# MAIN.net
KiCad netlist of a schematic drawn in Altium Designer
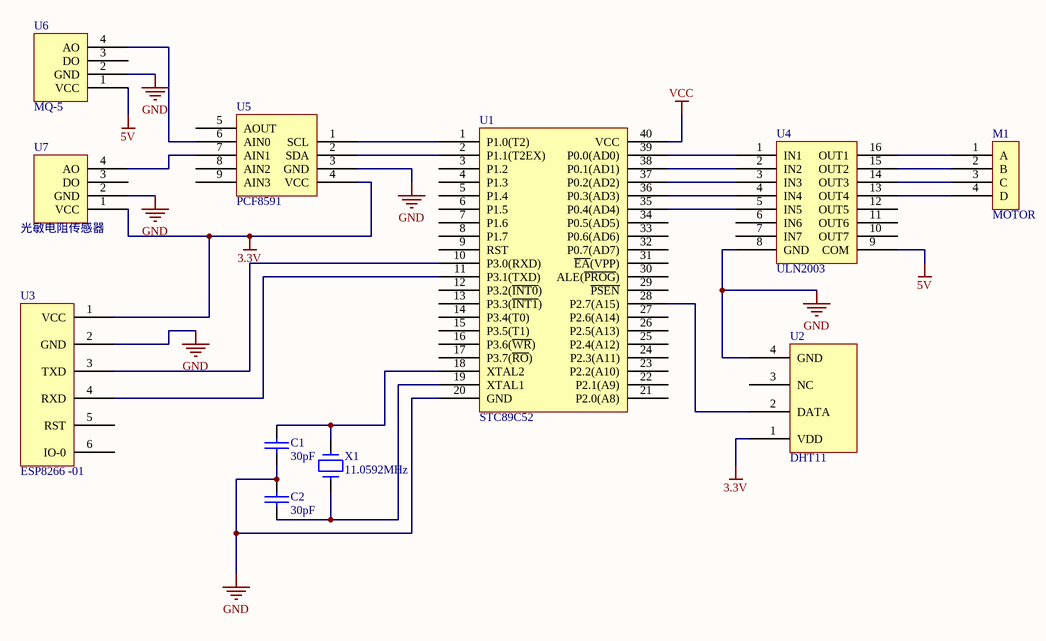
[diagram p0: MAIN.SchDoc]

(export (version "E")
  (design (tool "Eeschema 10.0.6"))
  (components
    (comp (ref "C1") (value "30pF") (footprint "RAD-0.1") (libsource (lib "温度") (part "CAP")))
    (comp (ref "C2") (value "30pF") (footprint "RAD-0.1") (libsource (lib "温度") (part "CAP")))
    (comp (ref "M1") (value "MOTOR") (libsource (lib "main") (part "MOTOR")))
    (comp (ref "U1") (value "STC89C52") (footprint "DIP40") (libsource (lib "温度") (part "89C52")))
    (comp (ref "U2") (value "DHT11") (footprint "P04A") (libsource (lib "main") (part "DHT11")))
    (comp (ref "U3") (value "ESP8266 -01") (footprint "P04A") (libsource (lib "main") (part "ESP8266 -01")))
    (comp (ref "U4") (value "ULN2003") (libsource (lib "main") (part "ULN2003")))
    (comp (ref "U5") (value "PCF8591") (libsource (lib "main") (part "PCF8591")))
    (comp (ref "U6") (value "MQ-5") (libsource (lib "main") (part "MQ-5")))
    (comp (ref "U7") (value "光敏电阻传感器") (libsource (lib "main") (part "光敏电阻传感器")))
    (comp (ref "X1") (value "11.0592MHz") (footprint "XTAL") (libsource (lib "温度") (part "CRYSTAL")))
  )
  (nets
    (net (code "1") (name "3.3V") (class "Default")
      (node (ref "U2") (pin "1") (pinfunction "VDD_1") (pintype "passive"))
      (node (ref "U3") (pin "1") (pinfunction "VCC_1") (pintype "passive"))
      (node (ref "U5") (pin "4") (pinfunction "VCC_4") (pintype "passive"))
      (node (ref "U7") (pin "1") (pinfunction "VCC_1") (pintype "passive"))
    )
    (net (code "2") (name "5V") (class "Default")
      (node (ref "U4") (pin "9") (pinfunction "COM_9") (pintype "passive"))
      (node (ref "U6") (pin "1") (pinfunction "VCC_1") (pintype "passive"))
    )
    (net (code "3") (name "GND") (class "Default")
      (node (ref "C1") (pin "2") (pinfunction "2_2") (pintype "passive"))
      (node (ref "C2") (pin "1") (pinfunction "1_1") (pintype "passive"))
      (node (ref "U1") (pin "20") (pinfunction "GND_20") (pintype "passive"))
      (node (ref "U2") (pin "4") (pinfunction "GND_4") (pintype "passive"))
      (node (ref "U3") (pin "2") (pinfunction "GND_2") (pintype "passive"))
      (node (ref "U4") (pin "8") (pinfunction "GND_8") (pintype "passive"))
      (node (ref "U5") (pin "3") (pinfunction "GND_3") (pintype "passive"))
      (node (ref "U6") (pin "2") (pinfunction "GND_2") (pintype "passive"))
      (node (ref "U7") (pin "2") (pinfunction "GND_2") (pintype "passive"))
    )
    (net (code "4") (name "Net-(M1-A)") (class "Default")
      (node (ref "M1") (pin "1") (pinfunction "A_1") (pintype "passive"))
      (node (ref "U4") (pin "16") (pinfunction "OUT1_16") (pintype "passive"))
    )
    (net (code "5") (name "Net-(M1-B)") (class "Default")
      (node (ref "M1") (pin "2") (pinfunction "B_2") (pintype "passive"))
      (node (ref "U4") (pin "15") (pinfunction "OUT2_15") (pintype "passive"))
    )
    (net (code "6") (name "Net-(M1-C)") (class "Default")
      (node (ref "M1") (pin "3") (pinfunction "C_3") (pintype "passive"))
      (node (ref "U4") (pin "14") (pinfunction "OUT3_14") (pintype "passive"))
    )
    (net (code "7") (name "Net-(M1-D)") (class "Default")
      (node (ref "M1") (pin "4") (pinfunction "D_4") (pintype "passive"))
      (node (ref "U4") (pin "13") (pinfunction "OUT4_13") (pintype "passive"))
    )
    (net (code "8") (name "Net-(U1-P0.0(AD0))") (class "Default")
      (node (ref "U1") (pin "39") (pinfunction "P0.0(AD0)_39") (pintype "passive"))
      (node (ref "U4") (pin "1") (pinfunction "IN1_1") (pintype "passive"))
    )
    (net (code "9") (name "Net-(U1-P0.1(AD1))") (class "Default")
      (node (ref "U1") (pin "38") (pinfunction "P0.1(AD1)_38") (pintype "passive"))
      (node (ref "U4") (pin "2") (pinfunction "IN2_2") (pintype "passive"))
    )
    (net (code "10") (name "Net-(U1-P0.2(AD2))") (class "Default")
      (node (ref "U1") (pin "37") (pinfunction "P0.2(AD2)_37") (pintype "passive"))
      (node (ref "U4") (pin "3") (pinfunction "IN3_3") (pintype "passive"))
    )
    (net (code "11") (name "Net-(U1-P0.3(AD3))") (class "Default")
      (node (ref "U1") (pin "36") (pinfunction "P0.3(AD3)_36") (pintype "passive"))
      (node (ref "U4") (pin "4") (pinfunction "IN4_4") (pintype "passive"))
    )
    (net (code "12") (name "Net-(U1-P0.4(AD4))") (class "Default")
      (node (ref "U1") (pin "35") (pinfunction "P0.4(AD4)_35") (pintype "passive"))
      (node (ref "U4") (pin "5") (pinfunction "IN5_5") (pintype "passive"))
    )
    (net (code "13") (name "Net-(U1-P1.0(T2))") (class "Default")
      (node (ref "U1") (pin "1") (pinfunction "P1.0(T2)_1") (pintype "passive"))
      (node (ref "U5") (pin "1") (pinfunction "SCL_1") (pintype "passive"))
    )
    (net (code "14") (name "Net-(U1-P1.1(T2EX))") (class "Default")
      (node (ref "U1") (pin "2") (pinfunction "P1.1(T2EX)_2") (pintype "passive"))
      (node (ref "U5") (pin "2") (pinfunction "SDA_2") (pintype "passive"))
    )
    (net (code "15") (name "Net-(U1-P2.7(A15))") (class "Default")
      (node (ref "U1") (pin "28") (pinfunction "P2.7(A15)_28") (pintype "passive"))
      (node (ref "U2") (pin "2") (pinfunction "DATA_2") (pintype "passive"))
    )
    (net (code "16") (name "Net-(U1-P3.0(RXD))") (class "Default")
      (node (ref "U1") (pin "10") (pinfunction "P3.0(RXD)_10") (pintype "passive"))
      (node (ref "U3") (pin "3") (pinfunction "TXD_3") (pintype "passive"))
    )
    (net (code "17") (name "Net-(U1-P3.1(TXD))") (class "Default")
      (node (ref "U1") (pin "11") (pinfunction "P3.1(TXD)_11") (pintype "passive"))
      (node (ref "U3") (pin "4") (pinfunction "RXD_4") (pintype "passive"))
    )
    (net (code "18") (name "Net-(U1-XTAL1)") (class "Default")
      (node (ref "C2") (pin "2") (pinfunction "2_2") (pintype "passive"))
      (node (ref "U1") (pin "19") (pinfunction "XTAL1_19") (pintype "passive"))
      (node (ref "X1") (pin "2") (pinfunction "2_2") (pintype "passive"))
    )
    (net (code "19") (name "Net-(U1-XTAL2)") (class "Default")
      (node (ref "C1") (pin "1") (pinfunction "1_1") (pintype "passive"))
      (node (ref "U1") (pin "18") (pinfunction "XTAL2_18") (pintype "passive"))
      (node (ref "X1") (pin "1") (pinfunction "1_1") (pintype "passive"))
    )
    (net (code "20") (name "Net-(U5-AIN0)") (class "Default")
      (node (ref "U5") (pin "6") (pinfunction "AIN0_6") (pintype "passive"))
      (node (ref "U6") (pin "4") (pinfunction "AO_4") (pintype "passive"))
    )
    (net (code "21") (name "Net-(U5-AIN1)") (class "Default")
      (node (ref "U5") (pin "7") (pinfunction "AIN1_7") (pintype "passive"))
      (node (ref "U7") (pin "4") (pinfunction "AO_4") (pintype "passive"))
    )
    (net (code "22") (name "VCC") (class "Default")
      (node (ref "U1") (pin "40") (pinfunction "VCC_40") (pintype "passive"))
    )
    (net (code "23") (name "unconnected-(U1-ALE(~{PROG})-Pad30)") (class "Default")
      (node (ref "U1") (pin "30") (pinfunction "ALE(~{PROG})_30") (pintype "passive"))
    )
    (net (code "24") (name "unconnected-(U1-P0.5(AD5)-Pad34)") (class "Default")
      (node (ref "U1") (pin "34") (pinfunction "P0.5(AD5)_34") (pintype "passive"))
    )
    (net (code "25") (name "unconnected-(U1-P0.6(AD6)-Pad33)") (class "Default")
      (node (ref "U1") (pin "33") (pinfunction "P0.6(AD6)_33") (pintype "passive"))
    )
    (net (code "26") (name "unconnected-(U1-P0.7(AD7)-Pad32)") (class "Default")
      (node (ref "U1") (pin "32") (pinfunction "P0.7(AD7)_32") (pintype "passive"))
    )
    (net (code "27") (name "unconnected-(U1-P1.2-Pad3)") (class "Default")
      (node (ref "U1") (pin "3") (pinfunction "P1.2_3") (pintype "passive"))
    )
    (net (code "28") (name "unconnected-(U1-P1.3-Pad4)") (class "Default")
      (node (ref "U1") (pin "4") (pinfunction "P1.3_4") (pintype "passive"))
    )
    (net (code "29") (name "unconnected-(U1-P1.4-Pad5)") (class "Default")
      (node (ref "U1") (pin "5") (pinfunction "P1.4_5") (pintype "passive"))
    )
    (net (code "30") (name "unconnected-(U1-P1.5-Pad6)") (class "Default")
      (node (ref "U1") (pin "6") (pinfunction "P1.5_6") (pintype "passive"))
    )
    (net (code "31") (name "unconnected-(U1-P1.6-Pad7)") (class "Default")
      (node (ref "U1") (pin "7") (pinfunction "P1.6_7") (pintype "passive"))
    )
    (net (code "32") (name "unconnected-(U1-P1.7-Pad8)") (class "Default")
      (node (ref "U1") (pin "8") (pinfunction "P1.7_8") (pintype "passive"))
    )
    (net (code "33") (name "unconnected-(U1-P2.0(A8)-Pad21)") (class "Default")
      (node (ref "U1") (pin "21") (pinfunction "P2.0(A8)_21") (pintype "passive"))
    )
    (net (code "34") (name "unconnected-(U1-P2.1(A9)-Pad22)") (class "Default")
      (node (ref "U1") (pin "22") (pinfunction "P2.1(A9)_22") (pintype "passive"))
    )
    (net (code "35") (name "unconnected-(U1-P2.2(A10)-Pad23)") (class "Default")
      (node (ref "U1") (pin "23") (pinfunction "P2.2(A10)_23") (pintype "passive"))
    )
    (net (code "36") (name "unconnected-(U1-P2.3(A11)-Pad24)") (class "Default")
      (node (ref "U1") (pin "24") (pinfunction "P2.3(A11)_24") (pintype "passive"))
    )
    (net (code "37") (name "unconnected-(U1-P2.4(A12)-Pad25)") (class "Default")
      (node (ref "U1") (pin "25") (pinfunction "P2.4(A12)_25") (pintype "passive"))
    )
    (net (code "38") (name "unconnected-(U1-P2.5(A13)-Pad26)") (class "Default")
      (node (ref "U1") (pin "26") (pinfunction "P2.5(A13)_26") (pintype "passive"))
    )
    (net (code "39") (name "unconnected-(U1-P2.6(A14)-Pad27)") (class "Default")
      (node (ref "U1") (pin "27") (pinfunction "P2.6(A14)_27") (pintype "passive"))
    )
    (net (code "40") (name "unconnected-(U1-P3.2(~{INT0})-Pad12)") (class "Default")
      (node (ref "U1") (pin "12") (pinfunction "P3.2(~{INT0})_12") (pintype "passive"))
    )
    (net (code "41") (name "unconnected-(U1-P3.3(~{INT1})-Pad13)") (class "Default")
      (node (ref "U1") (pin "13") (pinfunction "P3.3(~{INT1})_13") (pintype "passive"))
    )
    (net (code "42") (name "unconnected-(U1-P3.4(T0)-Pad14)") (class "Default")
      (node (ref "U1") (pin "14") (pinfunction "P3.4(T0)_14") (pintype "passive"))
    )
    (net (code "43") (name "unconnected-(U1-P3.5(T1)-Pad15)") (class "Default")
      (node (ref "U1") (pin "15") (pinfunction "P3.5(T1)_15") (pintype "passive"))
    )
    (net (code "44") (name "unconnected-(U1-P3.6(~{WR})-Pad16)") (class "Default")
      (node (ref "U1") (pin "16") (pinfunction "P3.6(~{WR})_16") (pintype "passive"))
    )
    (net (code "45") (name "unconnected-(U1-P3.7(~{RO})-Pad17)") (class "Default")
      (node (ref "U1") (pin "17") (pinfunction "P3.7(~{RO})_17") (pintype "passive"))
    )
    (net (code "46") (name "unconnected-(U1-RST-Pad9)") (class "Default")
      (node (ref "U1") (pin "9") (pinfunction "RST_9") (pintype "passive"))
    )
    (net (code "47") (name "unconnected-(U1-~{EA}(VPP)-Pad31)") (class "Default")
      (node (ref "U1") (pin "31") (pinfunction "~{EA}(VPP)_31") (pintype "passive"))
    )
    (net (code "48") (name "unconnected-(U1-~{PSEN}-Pad29)") (class "Default")
      (node (ref "U1") (pin "29") (pinfunction "~{PSEN}_29") (pintype "passive"))
    )
    (net (code "49") (name "unconnected-(U2-NC-Pad3)") (class "Default")
      (node (ref "U2") (pin "3") (pinfunction "NC_3") (pintype "passive"))
    )
    (net (code "50") (name "unconnected-(U3-IO-0-Pad6)") (class "Default")
      (node (ref "U3") (pin "6") (pinfunction "IO-0_6") (pintype "passive"))
    )
    (net (code "51") (name "unconnected-(U3-RST-Pad5)") (class "Default")
      (node (ref "U3") (pin "5") (pinfunction "RST_5") (pintype "passive"))
    )
    (net (code "52") (name "unconnected-(U4-IN6-Pad6)") (class "Default")
      (node (ref "U4") (pin "6") (pinfunction "IN6_6") (pintype "passive"))
    )
    (net (code "53") (name "unconnected-(U4-IN7-Pad7)") (class "Default")
      (node (ref "U4") (pin "7") (pinfunction "IN7_7") (pintype "passive"))
    )
    (net (code "54") (name "unconnected-(U4-OUT5-Pad12)") (class "Default")
      (node (ref "U4") (pin "12") (pinfunction "OUT5_12") (pintype "passive"))
    )
    (net (code "55") (name "unconnected-(U4-OUT6-Pad11)") (class "Default")
      (node (ref "U4") (pin "11") (pinfunction "OUT6_11") (pintype "passive"))
    )
    (net (code "56") (name "unconnected-(U4-OUT7-Pad10)") (class "Default")
      (node (ref "U4") (pin "10") (pinfunction "OUT7_10") (pintype "passive"))
    )
    (net (code "57") (name "unconnected-(U5-AIN2-Pad8)") (class "Default")
      (node (ref "U5") (pin "8") (pinfunction "AIN2_8") (pintype "passive"))
    )
    (net (code "58") (name "unconnected-(U5-AIN3-Pad9)") (class "Default")
      (node (ref "U5") (pin "9") (pinfunction "AIN3_9") (pintype "passive"))
    )
    (net (code "59") (name "unconnected-(U5-AOUT-Pad5)") (class "Default")
      (node (ref "U5") (pin "5") (pinfunction "AOUT_5") (pintype "passive"))
    )
    (net (code "60") (name "unconnected-(U6-DO-Pad3)") (class "Default")
      (node (ref "U6") (pin "3") (pinfunction "DO_3") (pintype "passive"))
    )
    (net (code "61") (name "unconnected-(U7-DO-Pad3)") (class "Default")
      (node (ref "U7") (pin "3") (pinfunction "DO_3") (pintype "passive"))
    )
  )
)
